# 2030_LED_Driver.net
KiCad netlist of a schematic drawn in EAGLE
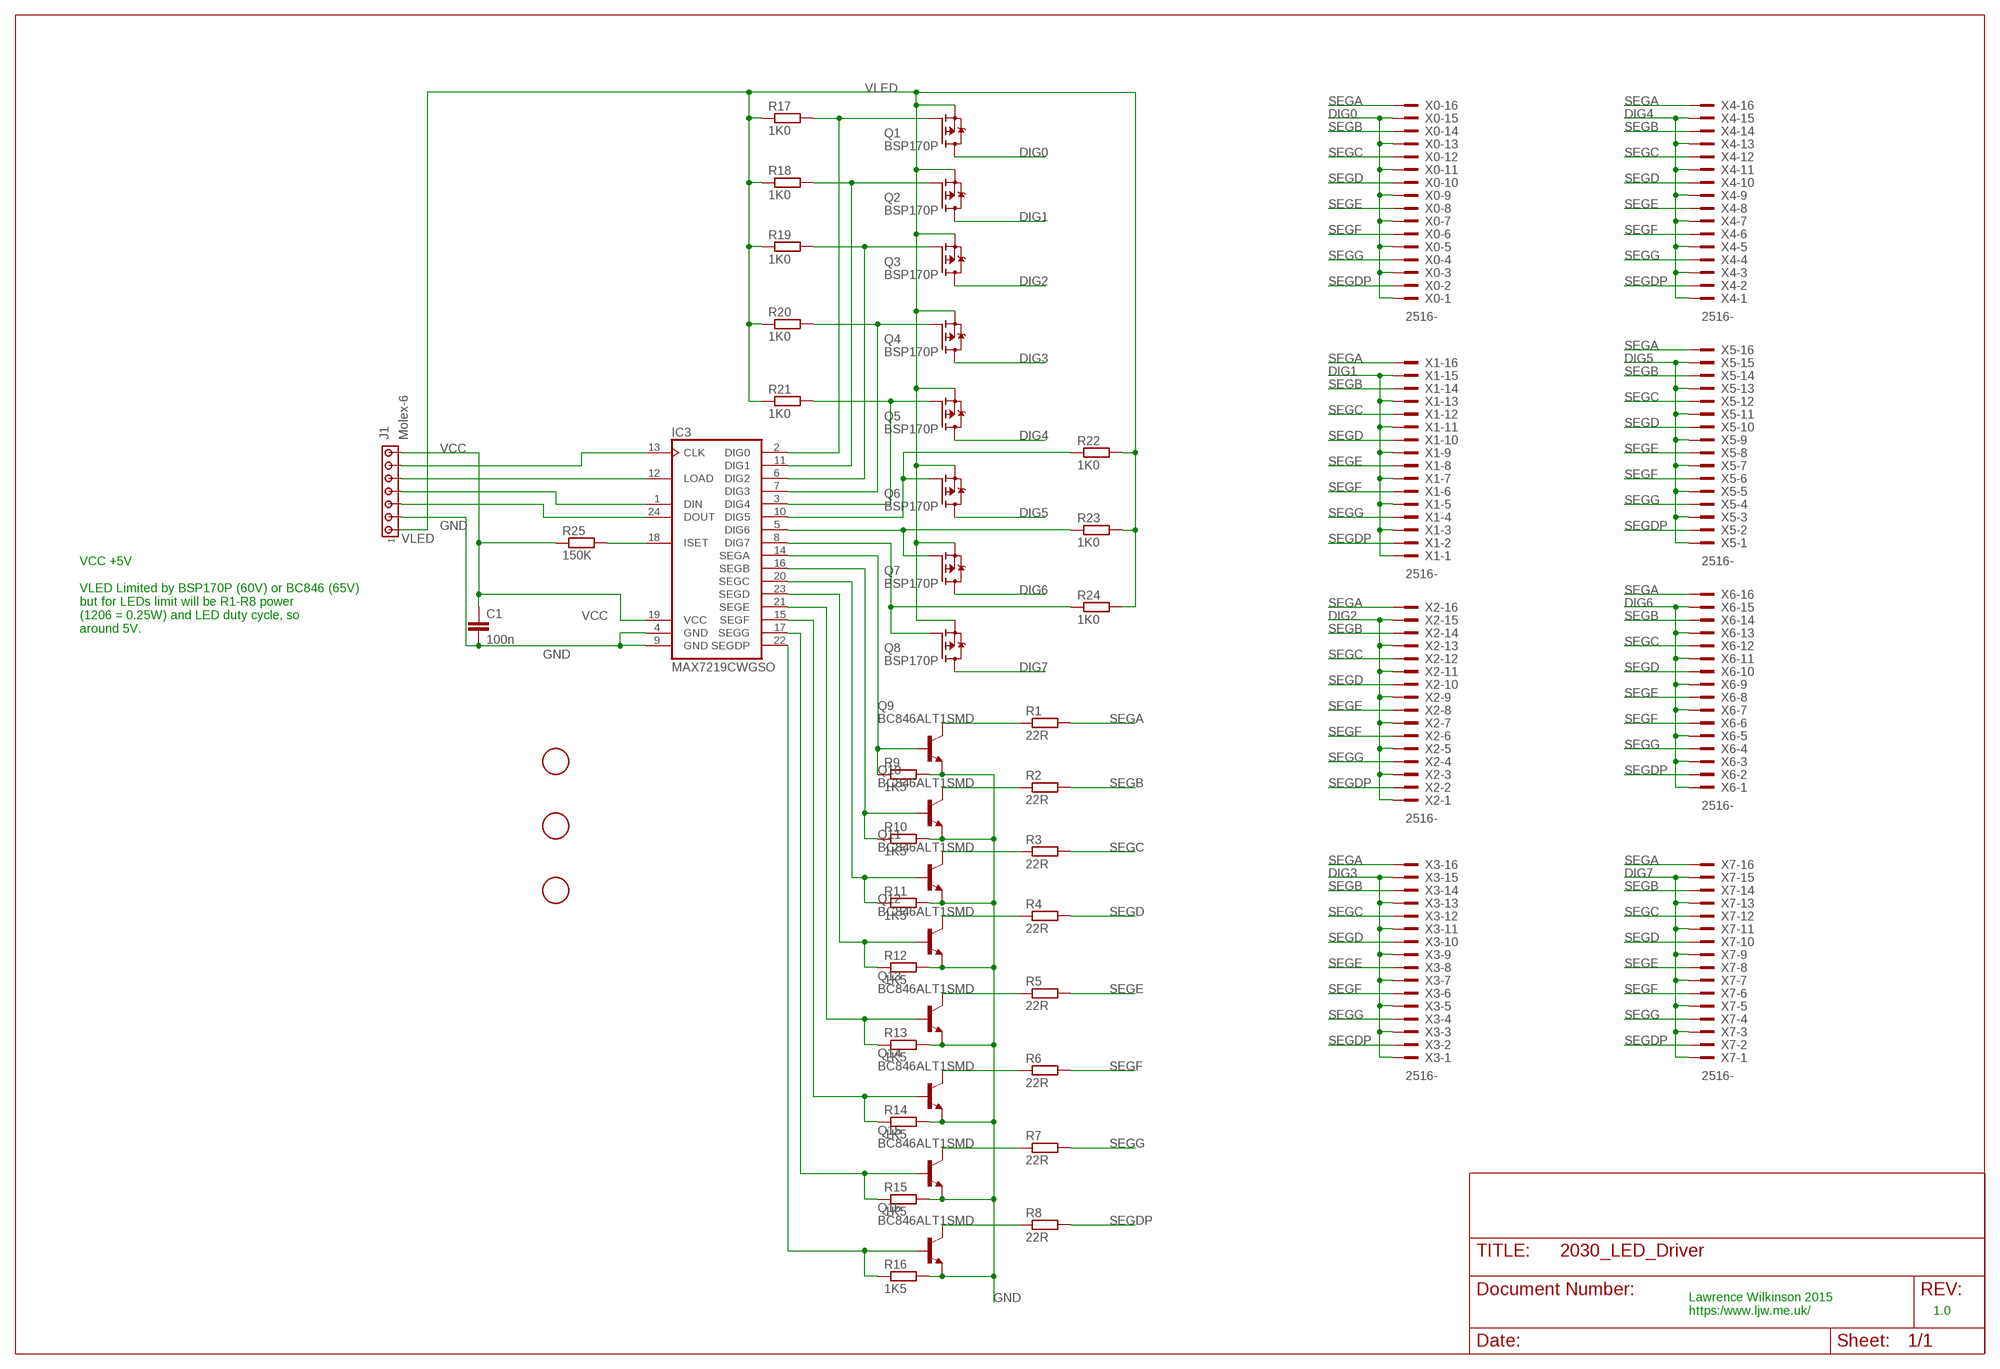
[diagram p0: schematic, sheet 1]

(export (version "E")
  (design (tool "Eeschema 10.0.6"))
  (components
    (comp (ref "C1")
      (value "100n")
      (footprint "eagle-import:C1206")
      (libsource (lib "eagle-import") (part "C-EUC1206"))
    )
    (comp (ref "IC3")
      (value "MAX7219CWGSO")
      (footprint "eagle-import:SO24L")
      (libsource (lib "eagle-import") (part "MAX7219CWGSO"))
    )
    (comp (ref "J1")
      (value "Molex-6")
      (footprint "eagle-import:10X07MTA")
      (libsource (lib "eagle-import") (part "MTA07-100"))
    )
    (comp (ref "Q1")
      (value "BSP170P")
      (footprint "eagle-import:SOT223")
      (libsource (lib "eagle-import") (part "BSP170P"))
    )
    (comp (ref "Q2")
      (value "BSP170P")
      (footprint "eagle-import:SOT223")
      (libsource (lib "eagle-import") (part "BSP170P"))
    )
    (comp (ref "Q3")
      (value "BSP170P")
      (footprint "eagle-import:SOT223")
      (libsource (lib "eagle-import") (part "BSP170P"))
    )
    (comp (ref "Q4")
      (value "BSP170P")
      (footprint "eagle-import:SOT223")
      (libsource (lib "eagle-import") (part "BSP170P"))
    )
    (comp (ref "Q5")
      (value "BSP170P")
      (footprint "eagle-import:SOT223")
      (libsource (lib "eagle-import") (part "BSP170P"))
    )
    (comp (ref "Q6")
      (value "BSP170P")
      (footprint "eagle-import:SOT223")
      (libsource (lib "eagle-import") (part "BSP170P"))
    )
    (comp (ref "Q7")
      (value "BSP170P")
      (footprint "eagle-import:SOT223")
      (libsource (lib "eagle-import") (part "BSP170P"))
    )
    (comp (ref "Q8")
      (value "BSP170P")
      (footprint "eagle-import:SOT223")
      (libsource (lib "eagle-import") (part "BSP170P"))
    )
    (comp (ref "Q9")
      (value "BC846ALT1SMD")
      (footprint "eagle-import:SOT23")
      (libsource (lib "eagle-import") (part "BC846SMDALT1"))
    )
    (comp (ref "Q10")
      (value "BC846ALT1SMD")
      (footprint "eagle-import:SOT23")
      (libsource (lib "eagle-import") (part "BC846SMDALT1"))
    )
    (comp (ref "Q11")
      (value "BC846ALT1SMD")
      (footprint "eagle-import:SOT23")
      (libsource (lib "eagle-import") (part "BC846SMDALT1"))
    )
    (comp (ref "Q12")
      (value "BC846ALT1SMD")
      (footprint "eagle-import:SOT23")
      (libsource (lib "eagle-import") (part "BC846SMDALT1"))
    )
    (comp (ref "Q13")
      (value "BC846ALT1SMD")
      (footprint "eagle-import:SOT23")
      (libsource (lib "eagle-import") (part "BC846SMDALT1"))
    )
    (comp (ref "Q14")
      (value "BC846ALT1SMD")
      (footprint "eagle-import:SOT23")
      (libsource (lib "eagle-import") (part "BC846SMDALT1"))
    )
    (comp (ref "Q15")
      (value "BC846ALT1SMD")
      (footprint "eagle-import:SOT23")
      (libsource (lib "eagle-import") (part "BC846SMDALT1"))
    )
    (comp (ref "Q16")
      (value "BC846ALT1SMD")
      (footprint "eagle-import:SOT23")
      (libsource (lib "eagle-import") (part "BC846SMDALT1"))
    )
    (comp (ref "R1")
      (value "22R")
      (footprint "eagle-import:M1206")
      (libsource (lib "eagle-import") (part "R-EU_M1206"))
    )
    (comp (ref "R2")
      (value "22R")
      (footprint "eagle-import:M1206")
      (libsource (lib "eagle-import") (part "R-EU_M1206"))
    )
    (comp (ref "R3")
      (value "22R")
      (footprint "eagle-import:M1206")
      (libsource (lib "eagle-import") (part "R-EU_M1206"))
    )
    (comp (ref "R4")
      (value "22R")
      (footprint "eagle-import:M1206")
      (libsource (lib "eagle-import") (part "R-EU_M1206"))
    )
    (comp (ref "R5")
      (value "22R")
      (footprint "eagle-import:M1206")
      (libsource (lib "eagle-import") (part "R-EU_M1206"))
    )
    (comp (ref "R6")
      (value "22R")
      (footprint "eagle-import:M1206")
      (libsource (lib "eagle-import") (part "R-EU_M1206"))
    )
    (comp (ref "R7")
      (value "22R")
      (footprint "eagle-import:M1206")
      (libsource (lib "eagle-import") (part "R-EU_M1206"))
    )
    (comp (ref "R8")
      (value "22R")
      (footprint "eagle-import:M1206")
      (libsource (lib "eagle-import") (part "R-EU_M1206"))
    )
    (comp (ref "R9")
      (value "1K5")
      (footprint "eagle-import:M0805")
      (libsource (lib "eagle-import") (part "R-EU_M0805"))
    )
    (comp (ref "R10")
      (value "1K5")
      (footprint "eagle-import:M0805")
      (libsource (lib "eagle-import") (part "R-EU_M0805"))
    )
    (comp (ref "R11")
      (value "1K5")
      (footprint "eagle-import:M0805")
      (libsource (lib "eagle-import") (part "R-EU_M0805"))
    )
    (comp (ref "R12")
      (value "1K5")
      (footprint "eagle-import:M0805")
      (libsource (lib "eagle-import") (part "R-EU_M0805"))
    )
    (comp (ref "R13")
      (value "1K5")
      (footprint "eagle-import:M0805")
      (libsource (lib "eagle-import") (part "R-EU_M0805"))
    )
    (comp (ref "R14")
      (value "1K5")
      (footprint "eagle-import:M0805")
      (libsource (lib "eagle-import") (part "R-EU_M0805"))
    )
    (comp (ref "R15")
      (value "1K5")
      (footprint "eagle-import:M0805")
      (libsource (lib "eagle-import") (part "R-EU_M0805"))
    )
    (comp (ref "R16")
      (value "1K5")
      (footprint "eagle-import:M0805")
      (libsource (lib "eagle-import") (part "R-EU_M0805"))
    )
    (comp (ref "R17")
      (value "1K0")
      (footprint "eagle-import:M0805")
      (libsource (lib "eagle-import") (part "R-EU_M0805"))
    )
    (comp (ref "R18")
      (value "1K0")
      (footprint "eagle-import:M0805")
      (libsource (lib "eagle-import") (part "R-EU_M0805"))
    )
    (comp (ref "R19")
      (value "1K0")
      (footprint "eagle-import:M0805")
      (libsource (lib "eagle-import") (part "R-EU_M0805"))
    )
    (comp (ref "R20")
      (value "1K0")
      (footprint "eagle-import:M0805")
      (libsource (lib "eagle-import") (part "R-EU_M0805"))
    )
    (comp (ref "R21")
      (value "1K0")
      (footprint "eagle-import:M0805")
      (libsource (lib "eagle-import") (part "R-EU_M0805"))
    )
    (comp (ref "R22")
      (value "1K0")
      (footprint "eagle-import:M0805")
      (libsource (lib "eagle-import") (part "R-EU_M0805"))
    )
    (comp (ref "R23")
      (value "1K0")
      (footprint "eagle-import:M0805")
      (libsource (lib "eagle-import") (part "R-EU_M0805"))
    )
    (comp (ref "R24")
      (value "1K0")
      (footprint "eagle-import:M0805")
      (libsource (lib "eagle-import") (part "R-EU_M0805"))
    )
    (comp (ref "R25")
      (value "150K")
      (footprint "eagle-import:M0805")
      (libsource (lib "eagle-import") (part "R-EU_M0805"))
    )
    (comp (ref "U$1")
      (value "FIDUCIAL")
      (footprint "eagle-import:FIDUCIAL_1MM")
      (libsource (lib "eagle-import") (part "FIDUCIAL"))
    )
    (comp (ref "U$2")
      (value "FIDUCIAL")
      (footprint "eagle-import:FIDUCIAL_1MM")
      (libsource (lib "eagle-import") (part "FIDUCIAL"))
    )
    (comp (ref "U$3")
      (value "FIDUCIAL")
      (footprint "eagle-import:FIDUCIAL_1MM")
      (libsource (lib "eagle-import") (part "FIDUCIAL"))
    )
    (comp (ref "X0")
      (value "2516-")
      (footprint "eagle-import:PAK100_2500-16")
      (libsource (lib "eagle-import") (part "2516-"))
    )
    (comp (ref "X1")
      (value "2516-")
      (footprint "eagle-import:PAK100_2500-16")
      (libsource (lib "eagle-import") (part "2516-"))
    )
    (comp (ref "X2")
      (value "2516-")
      (footprint "eagle-import:PAK100_2500-16")
      (libsource (lib "eagle-import") (part "2516-"))
    )
    (comp (ref "X3")
      (value "2516-")
      (footprint "eagle-import:PAK100_2500-16")
      (libsource (lib "eagle-import") (part "2516-"))
    )
    (comp (ref "X4")
      (value "2516-")
      (footprint "eagle-import:PAK100_2500-16")
      (libsource (lib "eagle-import") (part "2516-"))
    )
    (comp (ref "X5")
      (value "2516-")
      (footprint "eagle-import:PAK100_2500-16")
      (libsource (lib "eagle-import") (part "2516-"))
    )
    (comp (ref "X6")
      (value "2516-")
      (footprint "eagle-import:PAK100_2500-16")
      (libsource (lib "eagle-import") (part "2516-"))
    )
    (comp (ref "X7")
      (value "2516-")
      (footprint "eagle-import:PAK100_2500-16")
      (libsource (lib "eagle-import") (part "2516-"))
    )
  )
  (nets
    (net (code "1") (name "/DIG0") (class "Default")
      (node (ref "Q1") (pin "2") (pinfunction "D_2") (pintype "passive"))
      (node (ref "Q1") (pin "4") (pinfunction "D_4") (pintype "passive"))
      (node (ref "X0") (pin "1") (pinfunction "KL_1") (pintype "passive"))
      (node (ref "X0") (pin "11") (pinfunction "KL_11") (pintype "passive"))
      (node (ref "X0") (pin "13") (pinfunction "KL_13") (pintype "passive"))
      (node (ref "X0") (pin "15") (pinfunction "KL_15") (pintype "passive"))
      (node (ref "X0") (pin "3") (pinfunction "KL_3") (pintype "passive"))
      (node (ref "X0") (pin "5") (pinfunction "KL_5") (pintype "passive"))
      (node (ref "X0") (pin "7") (pinfunction "KL_7") (pintype "passive"))
      (node (ref "X0") (pin "9") (pinfunction "KL_9") (pintype "passive"))
    )
    (net (code "2") (name "/DIG1") (class "Default")
      (node (ref "Q2") (pin "2") (pinfunction "D_2") (pintype "passive"))
      (node (ref "Q2") (pin "4") (pinfunction "D_4") (pintype "passive"))
      (node (ref "X1") (pin "1") (pinfunction "KL_1") (pintype "passive"))
      (node (ref "X1") (pin "11") (pinfunction "KL_11") (pintype "passive"))
      (node (ref "X1") (pin "13") (pinfunction "KL_13") (pintype "passive"))
      (node (ref "X1") (pin "15") (pinfunction "KL_15") (pintype "passive"))
      (node (ref "X1") (pin "3") (pinfunction "KL_3") (pintype "passive"))
      (node (ref "X1") (pin "5") (pinfunction "KL_5") (pintype "passive"))
      (node (ref "X1") (pin "7") (pinfunction "KL_7") (pintype "passive"))
      (node (ref "X1") (pin "9") (pinfunction "KL_9") (pintype "passive"))
    )
    (net (code "3") (name "/DIG2") (class "Default")
      (node (ref "Q3") (pin "2") (pinfunction "D_2") (pintype "passive"))
      (node (ref "Q3") (pin "4") (pinfunction "D_4") (pintype "passive"))
      (node (ref "X2") (pin "1") (pinfunction "KL_1") (pintype "passive"))
      (node (ref "X2") (pin "11") (pinfunction "KL_11") (pintype "passive"))
      (node (ref "X2") (pin "13") (pinfunction "KL_13") (pintype "passive"))
      (node (ref "X2") (pin "15") (pinfunction "KL_15") (pintype "passive"))
      (node (ref "X2") (pin "3") (pinfunction "KL_3") (pintype "passive"))
      (node (ref "X2") (pin "5") (pinfunction "KL_5") (pintype "passive"))
      (node (ref "X2") (pin "7") (pinfunction "KL_7") (pintype "passive"))
      (node (ref "X2") (pin "9") (pinfunction "KL_9") (pintype "passive"))
    )
    (net (code "4") (name "/DIG3") (class "Default")
      (node (ref "Q4") (pin "2") (pinfunction "D_2") (pintype "passive"))
      (node (ref "Q4") (pin "4") (pinfunction "D_4") (pintype "passive"))
      (node (ref "X3") (pin "1") (pinfunction "KL_1") (pintype "passive"))
      (node (ref "X3") (pin "11") (pinfunction "KL_11") (pintype "passive"))
      (node (ref "X3") (pin "13") (pinfunction "KL_13") (pintype "passive"))
      (node (ref "X3") (pin "15") (pinfunction "KL_15") (pintype "passive"))
      (node (ref "X3") (pin "3") (pinfunction "KL_3") (pintype "passive"))
      (node (ref "X3") (pin "5") (pinfunction "KL_5") (pintype "passive"))
      (node (ref "X3") (pin "7") (pinfunction "KL_7") (pintype "passive"))
      (node (ref "X3") (pin "9") (pinfunction "KL_9") (pintype "passive"))
    )
    (net (code "5") (name "/DIG4") (class "Default")
      (node (ref "Q5") (pin "2") (pinfunction "D_2") (pintype "passive"))
      (node (ref "Q5") (pin "4") (pinfunction "D_4") (pintype "passive"))
      (node (ref "X4") (pin "1") (pinfunction "KL_1") (pintype "passive"))
      (node (ref "X4") (pin "11") (pinfunction "KL_11") (pintype "passive"))
      (node (ref "X4") (pin "13") (pinfunction "KL_13") (pintype "passive"))
      (node (ref "X4") (pin "15") (pinfunction "KL_15") (pintype "passive"))
      (node (ref "X4") (pin "3") (pinfunction "KL_3") (pintype "passive"))
      (node (ref "X4") (pin "5") (pinfunction "KL_5") (pintype "passive"))
      (node (ref "X4") (pin "7") (pinfunction "KL_7") (pintype "passive"))
      (node (ref "X4") (pin "9") (pinfunction "KL_9") (pintype "passive"))
    )
    (net (code "6") (name "/DIG5") (class "Default")
      (node (ref "Q6") (pin "2") (pinfunction "D_2") (pintype "passive"))
      (node (ref "Q6") (pin "4") (pinfunction "D_4") (pintype "passive"))
      (node (ref "X5") (pin "1") (pinfunction "KL_1") (pintype "passive"))
      (node (ref "X5") (pin "11") (pinfunction "KL_11") (pintype "passive"))
      (node (ref "X5") (pin "13") (pinfunction "KL_13") (pintype "passive"))
      (node (ref "X5") (pin "15") (pinfunction "KL_15") (pintype "passive"))
      (node (ref "X5") (pin "3") (pinfunction "KL_3") (pintype "passive"))
      (node (ref "X5") (pin "5") (pinfunction "KL_5") (pintype "passive"))
      (node (ref "X5") (pin "7") (pinfunction "KL_7") (pintype "passive"))
      (node (ref "X5") (pin "9") (pinfunction "KL_9") (pintype "passive"))
    )
    (net (code "7") (name "/DIG6") (class "Default")
      (node (ref "Q7") (pin "2") (pinfunction "D_2") (pintype "passive"))
      (node (ref "Q7") (pin "4") (pinfunction "D_4") (pintype "passive"))
      (node (ref "X6") (pin "1") (pinfunction "KL_1") (pintype "passive"))
      (node (ref "X6") (pin "11") (pinfunction "KL_11") (pintype "passive"))
      (node (ref "X6") (pin "13") (pinfunction "KL_13") (pintype "passive"))
      (node (ref "X6") (pin "15") (pinfunction "KL_15") (pintype "passive"))
      (node (ref "X6") (pin "3") (pinfunction "KL_3") (pintype "passive"))
      (node (ref "X6") (pin "5") (pinfunction "KL_5") (pintype "passive"))
      (node (ref "X6") (pin "7") (pinfunction "KL_7") (pintype "passive"))
      (node (ref "X6") (pin "9") (pinfunction "KL_9") (pintype "passive"))
    )
    (net (code "8") (name "/DIG7") (class "Default")
      (node (ref "Q8") (pin "2") (pinfunction "D_2") (pintype "passive"))
      (node (ref "Q8") (pin "4") (pinfunction "D_4") (pintype "passive"))
      (node (ref "X7") (pin "1") (pinfunction "KL_1") (pintype "passive"))
      (node (ref "X7") (pin "11") (pinfunction "KL_11") (pintype "passive"))
      (node (ref "X7") (pin "13") (pinfunction "KL_13") (pintype "passive"))
      (node (ref "X7") (pin "15") (pinfunction "KL_15") (pintype "passive"))
      (node (ref "X7") (pin "3") (pinfunction "KL_3") (pintype "passive"))
      (node (ref "X7") (pin "5") (pinfunction "KL_5") (pintype "passive"))
      (node (ref "X7") (pin "7") (pinfunction "KL_7") (pintype "passive"))
      (node (ref "X7") (pin "9") (pinfunction "KL_9") (pintype "passive"))
    )
    (net (code "9") (name "/GND") (class "Default")
      (node (ref "C1") (pin "2") (pinfunction "2_2") (pintype "passive"))
      (node (ref "IC3") (pin "4") (pinfunction "GND_4") (pintype "power_in"))
      (node (ref "IC3") (pin "9") (pinfunction "GND_9") (pintype "power_in"))
      (node (ref "J1") (pin "2") (pinfunction "2_2") (pintype "passive"))
      (node (ref "Q10") (pin "2") (pinfunction "E_2") (pintype "passive"))
      (node (ref "Q11") (pin "2") (pinfunction "E_2") (pintype "passive"))
      (node (ref "Q12") (pin "2") (pinfunction "E_2") (pintype "passive"))
      (node (ref "Q13") (pin "2") (pinfunction "E_2") (pintype "passive"))
      (node (ref "Q14") (pin "2") (pinfunction "E_2") (pintype "passive"))
      (node (ref "Q15") (pin "2") (pinfunction "E_2") (pintype "passive"))
      (node (ref "Q16") (pin "2") (pinfunction "E_2") (pintype "passive"))
      (node (ref "Q9") (pin "2") (pinfunction "E_2") (pintype "passive"))
      (node (ref "R10") (pin "2") (pinfunction "2_2") (pintype "passive"))
      (node (ref "R11") (pin "2") (pinfunction "2_2") (pintype "passive"))
      (node (ref "R12") (pin "2") (pinfunction "2_2") (pintype "passive"))
      (node (ref "R13") (pin "2") (pinfunction "2_2") (pintype "passive"))
      (node (ref "R14") (pin "2") (pinfunction "2_2") (pintype "passive"))
      (node (ref "R15") (pin "2") (pinfunction "2_2") (pintype "passive"))
      (node (ref "R16") (pin "2") (pinfunction "2_2") (pintype "passive"))
      (node (ref "R9") (pin "2") (pinfunction "2_2") (pintype "passive"))
    )
    (net (code "10") (name "/SEGA") (class "Default")
      (node (ref "R1") (pin "2") (pinfunction "2_2") (pintype "passive"))
      (node (ref "X0") (pin "16") (pinfunction "KL_16") (pintype "passive"))
      (node (ref "X1") (pin "16") (pinfunction "KL_16") (pintype "passive"))
      (node (ref "X2") (pin "16") (pinfunction "KL_16") (pintype "passive"))
      (node (ref "X3") (pin "16") (pinfunction "KL_16") (pintype "passive"))
      (node (ref "X4") (pin "16") (pinfunction "KL_16") (pintype "passive"))
      (node (ref "X5") (pin "16") (pinfunction "KL_16") (pintype "passive"))
      (node (ref "X6") (pin "16") (pinfunction "KL_16") (pintype "passive"))
      (node (ref "X7") (pin "16") (pinfunction "KL_16") (pintype "passive"))
    )
    (net (code "11") (name "/SEGB") (class "Default")
      (node (ref "R2") (pin "2") (pinfunction "2_2") (pintype "passive"))
      (node (ref "X0") (pin "14") (pinfunction "KL_14") (pintype "passive"))
      (node (ref "X1") (pin "14") (pinfunction "KL_14") (pintype "passive"))
      (node (ref "X2") (pin "14") (pinfunction "KL_14") (pintype "passive"))
      (node (ref "X3") (pin "14") (pinfunction "KL_14") (pintype "passive"))
      (node (ref "X4") (pin "14") (pinfunction "KL_14") (pintype "passive"))
      (node (ref "X5") (pin "14") (pinfunction "KL_14") (pintype "passive"))
      (node (ref "X6") (pin "14") (pinfunction "KL_14") (pintype "passive"))
      (node (ref "X7") (pin "14") (pinfunction "KL_14") (pintype "passive"))
    )
    (net (code "12") (name "/SEGC") (class "Default")
      (node (ref "R3") (pin "2") (pinfunction "2_2") (pintype "passive"))
      (node (ref "X0") (pin "12") (pinfunction "KL_12") (pintype "passive"))
      (node (ref "X1") (pin "12") (pinfunction "KL_12") (pintype "passive"))
      (node (ref "X2") (pin "12") (pinfunction "KL_12") (pintype "passive"))
      (node (ref "X3") (pin "12") (pinfunction "KL_12") (pintype "passive"))
      (node (ref "X4") (pin "12") (pinfunction "KL_12") (pintype "passive"))
      (node (ref "X5") (pin "12") (pinfunction "KL_12") (pintype "passive"))
      (node (ref "X6") (pin "12") (pinfunction "KL_12") (pintype "passive"))
      (node (ref "X7") (pin "12") (pinfunction "KL_12") (pintype "passive"))
    )
    (net (code "13") (name "/SEGD") (class "Default")
      (node (ref "R4") (pin "2") (pinfunction "2_2") (pintype "passive"))
      (node (ref "X0") (pin "10") (pinfunction "KL_10") (pintype "passive"))
      (node (ref "X1") (pin "10") (pinfunction "KL_10") (pintype "passive"))
      (node (ref "X2") (pin "10") (pinfunction "KL_10") (pintype "passive"))
      (node (ref "X3") (pin "10") (pinfunction "KL_10") (pintype "passive"))
      (node (ref "X4") (pin "10") (pinfunction "KL_10") (pintype "passive"))
      (node (ref "X5") (pin "10") (pinfunction "KL_10") (pintype "passive"))
      (node (ref "X6") (pin "10") (pinfunction "KL_10") (pintype "passive"))
      (node (ref "X7") (pin "10") (pinfunction "KL_10") (pintype "passive"))
    )
    (net (code "14") (name "/SEGDP") (class "Default")
      (node (ref "R8") (pin "2") (pinfunction "2_2") (pintype "passive"))
      (node (ref "X0") (pin "2") (pinfunction "KL_2") (pintype "passive"))
      (node (ref "X1") (pin "2") (pinfunction "KL_2") (pintype "passive"))
      (node (ref "X2") (pin "2") (pinfunction "KL_2") (pintype "passive"))
      (node (ref "X3") (pin "2") (pinfunction "KL_2") (pintype "passive"))
      (node (ref "X4") (pin "2") (pinfunction "KL_2") (pintype "passive"))
      (node (ref "X5") (pin "2") (pinfunction "KL_2") (pintype "passive"))
      (node (ref "X6") (pin "2") (pinfunction "KL_2") (pintype "passive"))
      (node (ref "X7") (pin "2") (pinfunction "KL_2") (pintype "passive"))
    )
    (net (code "15") (name "/SEGE") (class "Default")
      (node (ref "R5") (pin "2") (pinfunction "2_2") (pintype "passive"))
      (node (ref "X0") (pin "8") (pinfunction "KL_8") (pintype "passive"))
      (node (ref "X1") (pin "8") (pinfunction "KL_8") (pintype "passive"))
      (node (ref "X2") (pin "8") (pinfunction "KL_8") (pintype "passive"))
      (node (ref "X3") (pin "8") (pinfunction "KL_8") (pintype "passive"))
      (node (ref "X4") (pin "8") (pinfunction "KL_8") (pintype "passive"))
      (node (ref "X5") (pin "8") (pinfunction "KL_8") (pintype "passive"))
      (node (ref "X6") (pin "8") (pinfunction "KL_8") (pintype "passive"))
      (node (ref "X7") (pin "8") (pinfunction "KL_8") (pintype "passive"))
    )
    (net (code "16") (name "/SEGF") (class "Default")
      (node (ref "R6") (pin "2") (pinfunction "2_2") (pintype "passive"))
      (node (ref "X0") (pin "6") (pinfunction "KL_6") (pintype "passive"))
      (node (ref "X1") (pin "6") (pinfunction "KL_6") (pintype "passive"))
      (node (ref "X2") (pin "6") (pinfunction "KL_6") (pintype "passive"))
      (node (ref "X3") (pin "6") (pinfunction "KL_6") (pintype "passive"))
      (node (ref "X4") (pin "6") (pinfunction "KL_6") (pintype "passive"))
      (node (ref "X5") (pin "6") (pinfunction "KL_6") (pintype "passive"))
      (node (ref "X6") (pin "6") (pinfunction "KL_6") (pintype "passive"))
      (node (ref "X7") (pin "6") (pinfunction "KL_6") (pintype "passive"))
    )
    (net (code "17") (name "/SEGG") (class "Default")
      (node (ref "R7") (pin "2") (pinfunction "2_2") (pintype "passive"))
      (node (ref "X0") (pin "4") (pinfunction "KL_4") (pintype "passive"))
      (node (ref "X1") (pin "4") (pinfunction "KL_4") (pintype "passive"))
      (node (ref "X2") (pin "4") (pinfunction "KL_4") (pintype "passive"))
      (node (ref "X3") (pin "4") (pinfunction "KL_4") (pintype "passive"))
      (node (ref "X4") (pin "4") (pinfunction "KL_4") (pintype "passive"))
      (node (ref "X5") (pin "4") (pinfunction "KL_4") (pintype "passive"))
      (node (ref "X6") (pin "4") (pinfunction "KL_4") (pintype "passive"))
      (node (ref "X7") (pin "4") (pinfunction "KL_4") (pintype "passive"))
    )
    (net (code "18") (name "/VCC") (class "Default")
      (node (ref "C1") (pin "1") (pinfunction "1_1") (pintype "passive"))
      (node (ref "IC3") (pin "19") (pinfunction "VCC_19") (pintype "power_in"))
      (node (ref "J1") (pin "7") (pinfunction "7_7") (pintype "passive"))
      (node (ref "R25") (pin "1") (pinfunction "1_1") (pintype "passive"))
    )
    (net (code "19") (name "/VLED") (class "Default")
      (node (ref "J1") (pin "1") (pinfunction "1_1") (pintype "passive"))
      (node (ref "Q1") (pin "3") (pinfunction "S_3") (pintype "passive"))
      (node (ref "Q2") (pin "3") (pinfunction "S_3") (pintype "passive"))
      (node (ref "Q3") (pin "3") (pinfunction "S_3") (pintype "passive"))
      (node (ref "Q4") (pin "3") (pinfunction "S_3") (pintype "passive"))
      (node (ref "Q5") (pin "3") (pinfunction "S_3") (pintype "passive"))
      (node (ref "Q6") (pin "3") (pinfunction "S_3") (pintype "passive"))
      (node (ref "Q7") (pin "3") (pinfunction "S_3") (pintype "passive"))
      (node (ref "Q8") (pin "3") (pinfunction "S_3") (pintype "passive"))
      (node (ref "R17") (pin "1") (pinfunction "1_1") (pintype "passive"))
      (node (ref "R18") (pin "1") (pinfunction "1_1") (pintype "passive"))
      (node (ref "R19") (pin "1") (pinfunction "1_1") (pintype "passive"))
      (node (ref "R20") (pin "1") (pinfunction "1_1") (pintype "passive"))
      (node (ref "R21") (pin "1") (pinfunction "1_1") (pintype "passive"))
      (node (ref "R22") (pin "2") (pinfunction "2_2") (pintype "passive"))
      (node (ref "R23") (pin "2") (pinfunction "2_2") (pintype "passive"))
      (node (ref "R24") (pin "2") (pinfunction "2_2") (pintype "passive"))
    )
    (net (code "20") (name "Net-(IC3-CLK)") (class "Default")
      (node (ref "IC3") (pin "13") (pinfunction "CLK_13") (pintype "input"))
      (node (ref "J1") (pin "6") (pinfunction "6_6") (pintype "passive"))
    )
    (net (code "21") (name "Net-(IC3-DIG0)") (class "Default")
      (node (ref "IC3") (pin "2") (pinfunction "DIG0_2") (pintype "output"))
      (node (ref "Q1") (pin "1") (pinfunction "G_1") (pintype "passive"))
      (node (ref "R17") (pin "2") (pinfunction "2_2") (pintype "passive"))
    )
    (net (code "22") (name "Net-(IC3-DIG1)") (class "Default")
      (node (ref "IC3") (pin "11") (pinfunction "DIG1_11") (pintype "output"))
      (node (ref "Q2") (pin "1") (pinfunction "G_1") (pintype "passive"))
      (node (ref "R18") (pin "2") (pinfunction "2_2") (pintype "passive"))
    )
    (net (code "23") (name "Net-(IC3-DIG2)") (class "Default")
      (node (ref "IC3") (pin "6") (pinfunction "DIG2_6") (pintype "output"))
      (node (ref "Q3") (pin "1") (pinfunction "G_1") (pintype "passive"))
      (node (ref "R19") (pin "2") (pinfunction "2_2") (pintype "passive"))
    )
    (net (code "24") (name "Net-(IC3-DIG3)") (class "Default")
      (node (ref "IC3") (pin "7") (pinfunction "DIG3_7") (pintype "output"))
      (node (ref "Q4") (pin "1") (pinfunction "G_1") (pintype "passive"))
      (node (ref "R20") (pin "2") (pinfunction "2_2") (pintype "passive"))
    )
    (net (code "25") (name "Net-(IC3-DIG4)") (class "Default")
      (node (ref "IC3") (pin "3") (pinfunction "DIG4_3") (pintype "output"))
      (node (ref "Q5") (pin "1") (pinfunction "G_1") (pintype "passive"))
      (node (ref "R21") (pin "2") (pinfunction "2_2") (pintype "passive"))
    )
    (net (code "26") (name "Net-(IC3-DIG5)") (class "Default")
      (node (ref "IC3") (pin "10") (pinfunction "DIG5_10") (pintype "output"))
      (node (ref "Q6") (pin "1") (pinfunction "G_1") (pintype "passive"))
      (node (ref "R22") (pin "1") (pinfunction "1_1") (pintype "passive"))
    )
    (net (code "27") (name "Net-(IC3-DIG6)") (class "Default")
      (node (ref "IC3") (pin "5") (pinfunction "DIG6_5") (pintype "output"))
      (node (ref "Q7") (pin "1") (pinfunction "G_1") (pintype "passive"))
      (node (ref "R23") (pin "1") (pinfunction "1_1") (pintype "passive"))
    )
    (net (code "28") (name "Net-(IC3-DIG7)") (class "Default")
      (node (ref "IC3") (pin "8") (pinfunction "DIG7_8") (pintype "output"))
      (node (ref "Q8") (pin "1") (pinfunction "G_1") (pintype "passive"))
      (node (ref "R24") (pin "1") (pinfunction "1_1") (pintype "passive"))
    )
    (net (code "29") (name "Net-(IC3-DIN)") (class "Default")
      (node (ref "IC3") (pin "1") (pinfunction "DIN_1") (pintype "input"))
      (node (ref "J1") (pin "4") (pinfunction "4_4") (pintype "passive"))
    )
    (net (code "30") (name "Net-(IC3-DOUT)") (class "Default")
      (node (ref "IC3") (pin "24") (pinfunction "DOUT_24") (pintype "output"))
      (node (ref "J1") (pin "3") (pinfunction "3_3") (pintype "passive"))
    )
    (net (code "31") (name "Net-(IC3-ISET)") (class "Default")
      (node (ref "IC3") (pin "18") (pinfunction "ISET_18") (pintype "input"))
      (node (ref "R25") (pin "2") (pinfunction "2_2") (pintype "passive"))
    )
    (net (code "32") (name "Net-(IC3-LOAD)") (class "Default")
      (node (ref "IC3") (pin "12") (pinfunction "LOAD_12") (pintype "input"))
      (node (ref "J1") (pin "5") (pinfunction "5_5") (pintype "passive"))
    )
    (net (code "33") (name "Net-(IC3-SEGA)") (class "Default")
      (node (ref "IC3") (pin "14") (pinfunction "SEGA_14") (pintype "output"))
      (node (ref "Q9") (pin "1") (pinfunction "B_1") (pintype "passive"))
      (node (ref "R9") (pin "1") (pinfunction "1_1") (pintype "passive"))
    )
    (net (code "34") (name "Net-(IC3-SEGB)") (class "Default")
      (node (ref "IC3") (pin "16") (pinfunction "SEGB_16") (pintype "output"))
      (node (ref "Q10") (pin "1") (pinfunction "B_1") (pintype "passive"))
      (node (ref "R10") (pin "1") (pinfunction "1_1") (pintype "passive"))
    )
    (net (code "35") (name "Net-(IC3-SEGC)") (class "Default")
      (node (ref "IC3") (pin "20") (pinfunction "SEGC_20") (pintype "output"))
      (node (ref "Q11") (pin "1") (pinfunction "B_1") (pintype "passive"))
      (node (ref "R11") (pin "1") (pinfunction "1_1") (pintype "passive"))
    )
    (net (code "36") (name "Net-(IC3-SEGD)") (class "Default")
      (node (ref "IC3") (pin "23") (pinfunction "SEGD_23") (pintype "output"))
      (node (ref "Q12") (pin "1") (pinfunction "B_1") (pintype "passive"))
      (node (ref "R12") (pin "1") (pinfunction "1_1") (pintype "passive"))
    )
    (net (code "37") (name "Net-(IC3-SEGDP)") (class "Default")
      (node (ref "IC3") (pin "22") (pinfunction "SEGDP_22") (pintype "output"))
      (node (ref "Q16") (pin "1") (pinfunction "B_1") (pintype "passive"))
      (node (ref "R16") (pin "1") (pinfunction "1_1") (pintype "passive"))
    )
    (net (code "38") (name "Net-(IC3-SEGE)") (class "Default")
      (node (ref "IC3") (pin "21") (pinfunction "SEGE_21") (pintype "output"))
      (node (ref "Q13") (pin "1") (pinfunction "B_1") (pintype "passive"))
      (node (ref "R13") (pin "1") (pinfunction "1_1") (pintype "passive"))
    )
    (net (code "39") (name "Net-(IC3-SEGF)") (class "Default")
      (node (ref "IC3") (pin "15") (pinfunction "SEGF_15") (pintype "output"))
      (node (ref "Q14") (pin "1") (pinfunction "B_1") (pintype "passive"))
      (node (ref "R14") (pin "1") (pinfunction "1_1") (pintype "passive"))
    )
    (net (code "40") (name "Net-(IC3-SEGG)") (class "Default")
      (node (ref "IC3") (pin "17") (pinfunction "SEGG_17") (pintype "output"))
      (node (ref "Q15") (pin "1") (pinfunction "B_1") (pintype "passive"))
      (node (ref "R15") (pin "1") (pinfunction "1_1") (pintype "passive"))
    )
    (net (code "41") (name "Net-(Q9-C)") (class "Default")
      (node (ref "Q9") (pin "3") (pinfunction "C_3") (pintype "passive"))
      (node (ref "R1") (pin "1") (pinfunction "1_1") (pintype "passive"))
    )
    (net (code "42") (name "Net-(Q10-C)") (class "Default")
      (node (ref "Q10") (pin "3") (pinfunction "C_3") (pintype "passive"))
      (node (ref "R2") (pin "1") (pinfunction "1_1") (pintype "passive"))
    )
    (net (code "43") (name "Net-(Q11-C)") (class "Default")
      (node (ref "Q11") (pin "3") (pinfunction "C_3") (pintype "passive"))
      (node (ref "R3") (pin "1") (pinfunction "1_1") (pintype "passive"))
    )
    (net (code "44") (name "Net-(Q12-C)") (class "Default")
      (node (ref "Q12") (pin "3") (pinfunction "C_3") (pintype "passive"))
      (node (ref "R4") (pin "1") (pinfunction "1_1") (pintype "passive"))
    )
    (net (code "45") (name "Net-(Q13-C)") (class "Default")
      (node (ref "Q13") (pin "3") (pinfunction "C_3") (pintype "passive"))
      (node (ref "R5") (pin "1") (pinfunction "1_1") (pintype "passive"))
    )
    (net (code "46") (name "Net-(Q14-C)") (class "Default")
      (node (ref "Q14") (pin "3") (pinfunction "C_3") (pintype "passive"))
      (node (ref "R6") (pin "1") (pinfunction "1_1") (pintype "passive"))
    )
    (net (code "47") (name "Net-(Q15-C)") (class "Default")
      (node (ref "Q15") (pin "3") (pinfunction "C_3") (pintype "passive"))
      (node (ref "R7") (pin "1") (pinfunction "1_1") (pintype "passive"))
    )
    (net (code "48") (name "Net-(Q16-C)") (class "Default")
      (node (ref "Q16") (pin "3") (pinfunction "C_3") (pintype "passive"))
      (node (ref "R8") (pin "1") (pinfunction "1_1") (pintype "passive"))
    )
  )
)
